# PS_DDR.net
KiCad netlist of a schematic drawn in Altium Designer
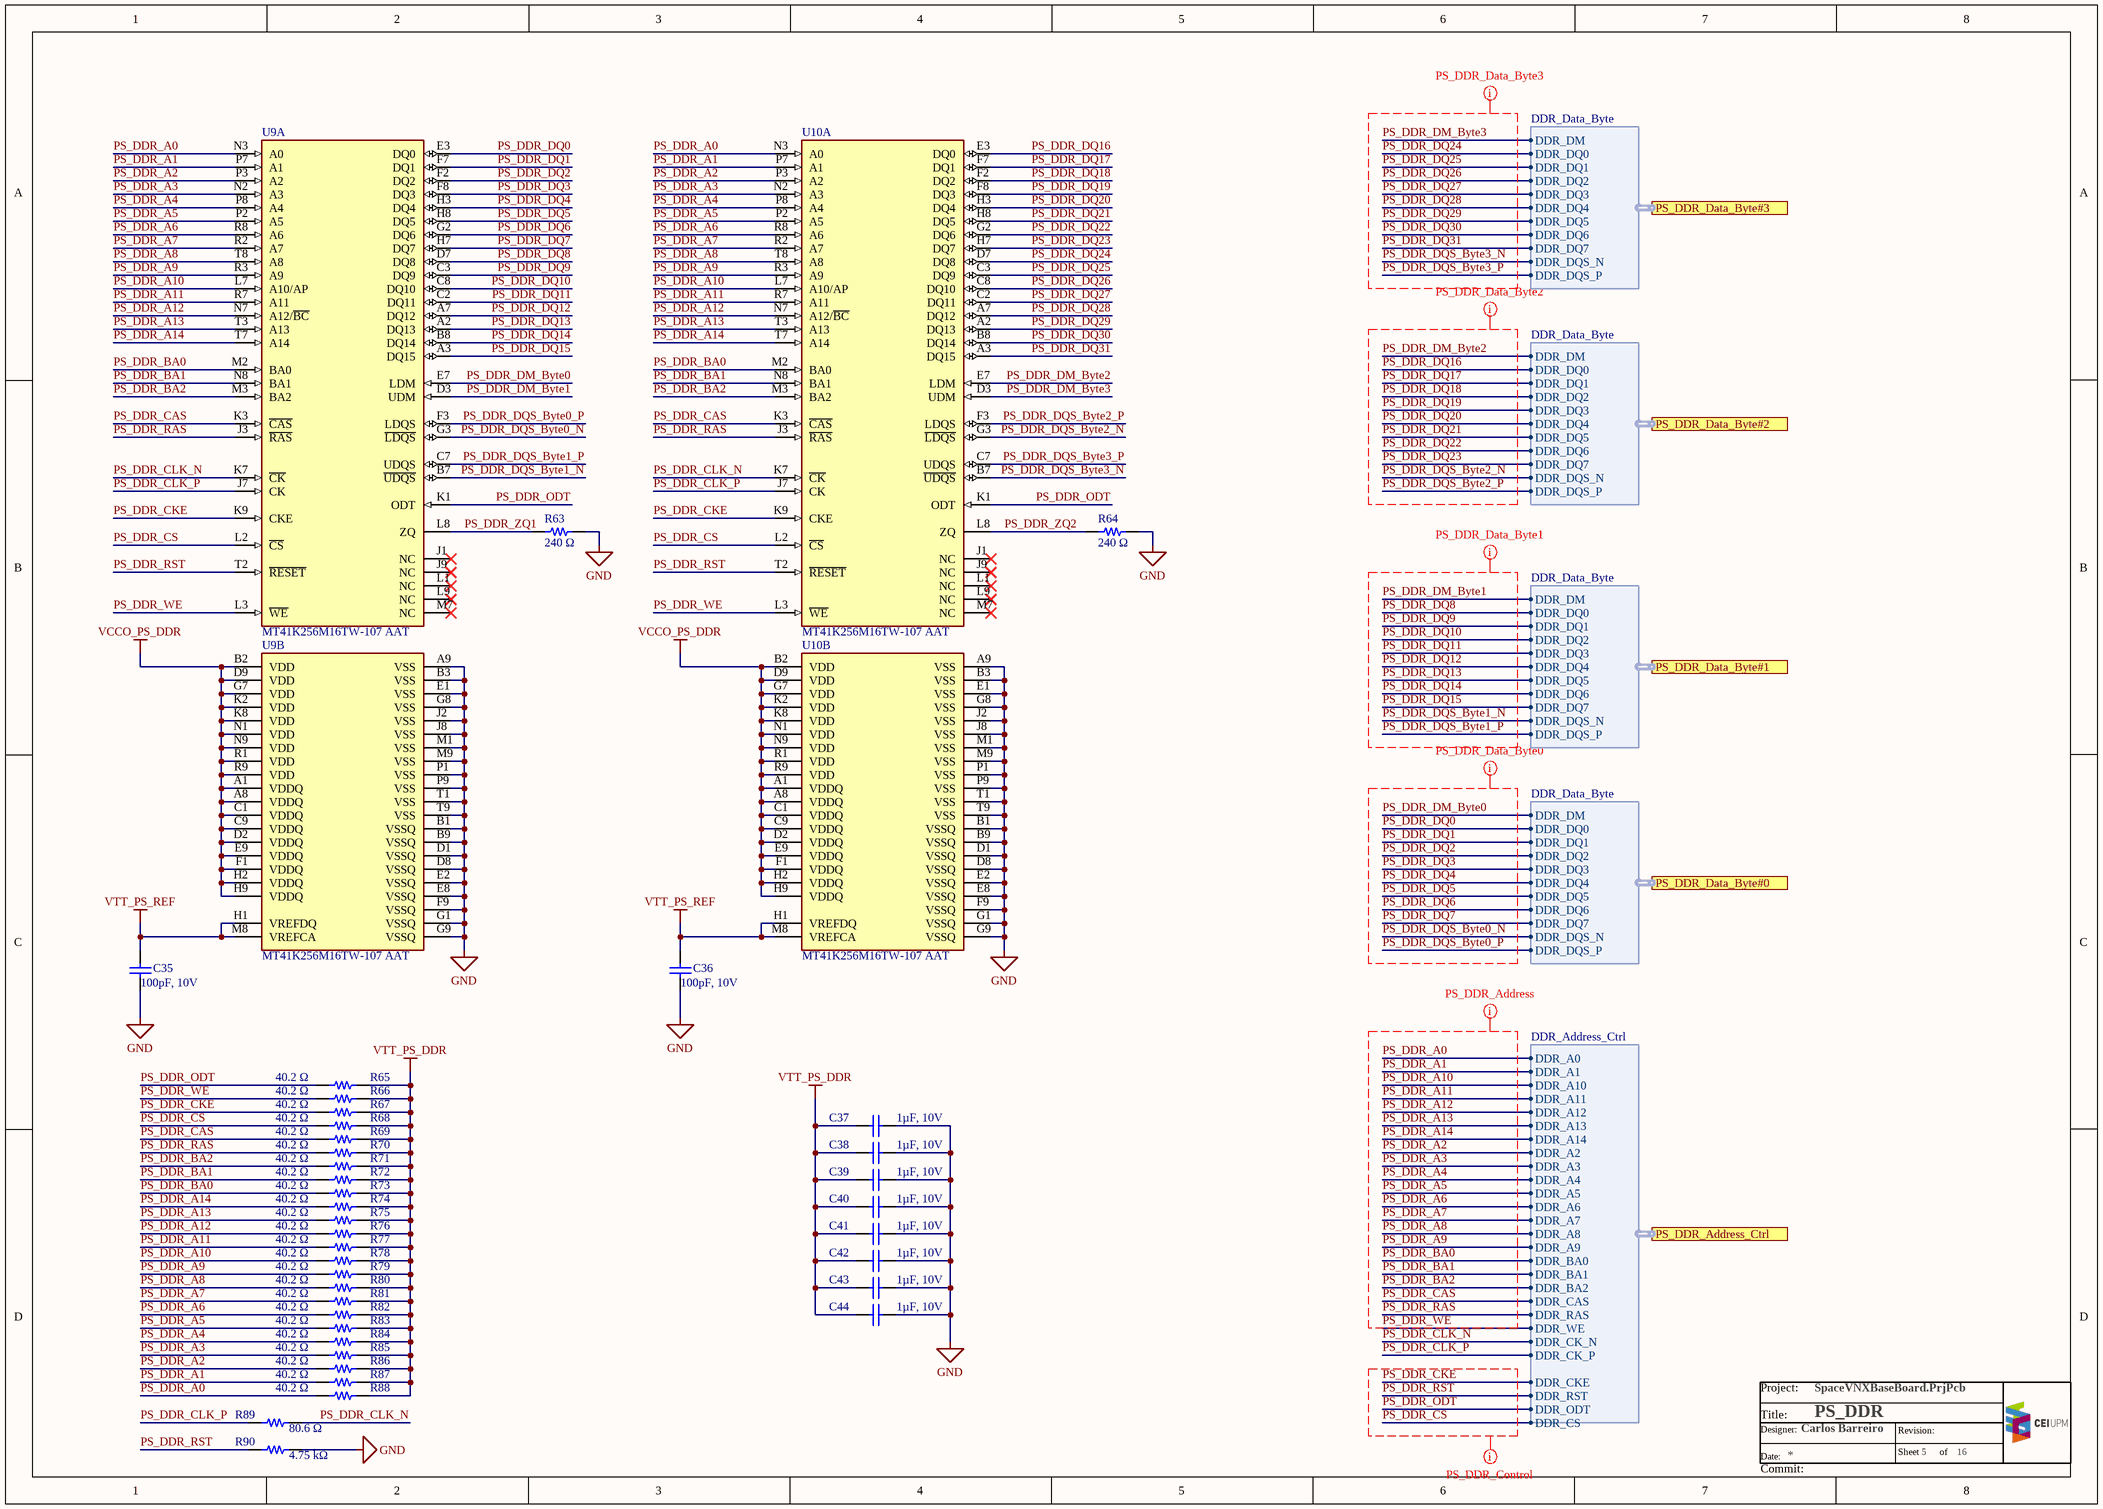
[diagram p0: PS_DDR.SchDoc]

(export (version "E")
  (design (tool "Eeschema 10.0.6"))
  (components
    (comp (ref "C35")
      (value "100pF, 10V")
      (footprint "WURTH_WCAP-CSGP_0402")
      (description "WCAP-CSGP Multilayer Ceramic Chip Capacitor, General Purpose, size 0402, NP0, 100pF, 10V")
      (fields
        (field (name "MANUFACTURER PART NUMBER") "885012005013")
        (field (name "MANUFACTURER") "Wurth Elektronik")
      )
      (libsource (lib "SpaceVNX") (part "885012005013"))
    )
    (comp (ref "C36")
      (value "100pF, 10V")
      (footprint "WURTH_WCAP-CSGP_0402")
      (description "WCAP-CSGP Multilayer Ceramic Chip Capacitor, General Purpose, size 0402, NP0, 100pF, 10V")
      (fields
        (field (name "MANUFACTURER PART NUMBER") "885012005013")
        (field (name "MANUFACTURER") "Wurth Elektronik")
      )
      (libsource (lib "SpaceVNX") (part "885012005013"))
    )
    (comp (ref "C37")
      (value "1µF, 10V")
      (footprint "WURTH_WCAP-CSGP_0402")
      (description "WCAP-CSGP Multilayer Ceramic Chip Capacitor, General Purpose, size 0402, X5R, 1uF, 10V")
      (fields
        (field (name "MANUFACTURER PART NUMBER") "885012105012")
        (field (name "MANUFACTURER") "Wurth Elektronik")
      )
      (libsource (lib "SpaceVNX") (part "885012105012"))
    )
    (comp (ref "C38")
      (value "1µF, 10V")
      (footprint "WURTH_WCAP-CSGP_0402")
      (description "WCAP-CSGP Multilayer Ceramic Chip Capacitor, General Purpose, size 0402, X5R, 1uF, 10V")
      (fields
        (field (name "MANUFACTURER PART NUMBER") "885012105012")
        (field (name "MANUFACTURER") "Wurth Elektronik")
      )
      (libsource (lib "SpaceVNX") (part "885012105012"))
    )
    (comp (ref "C39")
      (value "1µF, 10V")
      (footprint "WURTH_WCAP-CSGP_0402")
      (description "WCAP-CSGP Multilayer Ceramic Chip Capacitor, General Purpose, size 0402, X5R, 1uF, 10V")
      (fields
        (field (name "MANUFACTURER PART NUMBER") "885012105012")
        (field (name "MANUFACTURER") "Wurth Elektronik")
      )
      (libsource (lib "SpaceVNX") (part "885012105012"))
    )
    (comp (ref "C40")
      (value "1µF, 10V")
      (footprint "WURTH_WCAP-CSGP_0402")
      (description "WCAP-CSGP Multilayer Ceramic Chip Capacitor, General Purpose, size 0402, X5R, 1uF, 10V")
      (fields
        (field (name "MANUFACTURER PART NUMBER") "885012105012")
        (field (name "MANUFACTURER") "Wurth Elektronik")
      )
      (libsource (lib "SpaceVNX") (part "885012105012"))
    )
    (comp (ref "C41")
      (value "1µF, 10V")
      (footprint "WURTH_WCAP-CSGP_0402")
      (description "WCAP-CSGP Multilayer Ceramic Chip Capacitor, General Purpose, size 0402, X5R, 1uF, 10V")
      (fields
        (field (name "MANUFACTURER PART NUMBER") "885012105012")
        (field (name "MANUFACTURER") "Wurth Elektronik")
      )
      (libsource (lib "SpaceVNX") (part "885012105012"))
    )
    (comp (ref "C42")
      (value "1µF, 10V")
      (footprint "WURTH_WCAP-CSGP_0402")
      (description "WCAP-CSGP Multilayer Ceramic Chip Capacitor, General Purpose, size 0402, X5R, 1uF, 10V")
      (fields
        (field (name "MANUFACTURER PART NUMBER") "885012105012")
        (field (name "MANUFACTURER") "Wurth Elektronik")
      )
      (libsource (lib "SpaceVNX") (part "885012105012"))
    )
    (comp (ref "C43")
      (value "1µF, 10V")
      (footprint "WURTH_WCAP-CSGP_0402")
      (description "WCAP-CSGP Multilayer Ceramic Chip Capacitor, General Purpose, size 0402, X5R, 1uF, 10V")
      (fields
        (field (name "MANUFACTURER PART NUMBER") "885012105012")
        (field (name "MANUFACTURER") "Wurth Elektronik")
      )
      (libsource (lib "SpaceVNX") (part "885012105012"))
    )
    (comp (ref "C44")
      (value "1µF, 10V")
      (footprint "WURTH_WCAP-CSGP_0402")
      (description "WCAP-CSGP Multilayer Ceramic Chip Capacitor, General Purpose, size 0402, X5R, 1uF, 10V")
      (fields
        (field (name "MANUFACTURER PART NUMBER") "885012105012")
        (field (name "MANUFACTURER") "Wurth Elektronik")
      )
      (libsource (lib "SpaceVNX") (part "885012105012"))
    )
    (comp (ref "R63")
      (value "240 Ω")
      (footprint "PANASONIC_ERJ2G_0402")
      (description "General Purpose Thick Film Chip Resistors")
      (fields (field (name "MANUFACTURER") "Panasonic"))
      (libsource (lib "SpaceVNX") (part "ERJ2GEJ241X"))
    )
    (comp (ref "R64")
      (value "240 Ω")
      (footprint "PANASONIC_ERJ2G_0402")
      (description "General Purpose Thick Film Chip Resistors")
      (fields (field (name "MANUFACTURER") "Panasonic"))
      (libsource (lib "SpaceVNX") (part "ERJ2GEJ241X"))
    )
    (comp (ref "R65")
      (value "40.2 Ω")
      (footprint "PANASONIC_ERJ2G_0402")
      (description "General Purpose Thick Film Chip Resistors")
      (fields (field (name "MANUFACTURER") "Panasonic"))
      (libsource (lib "SpaceVNX") (part "ERJ2RKF40R2X"))
    )
    (comp (ref "R66")
      (value "40.2 Ω")
      (footprint "PANASONIC_ERJ2G_0402")
      (description "General Purpose Thick Film Chip Resistors")
      (fields (field (name "MANUFACTURER") "Panasonic"))
      (libsource (lib "SpaceVNX") (part "ERJ2RKF40R2X"))
    )
    (comp (ref "R67")
      (value "40.2 Ω")
      (footprint "PANASONIC_ERJ2G_0402")
      (description "General Purpose Thick Film Chip Resistors")
      (fields (field (name "MANUFACTURER") "Panasonic"))
      (libsource (lib "SpaceVNX") (part "ERJ2RKF40R2X"))
    )
    (comp (ref "R68")
      (value "40.2 Ω")
      (footprint "PANASONIC_ERJ2G_0402")
      (description "General Purpose Thick Film Chip Resistors")
      (fields (field (name "MANUFACTURER") "Panasonic"))
      (libsource (lib "SpaceVNX") (part "ERJ2RKF40R2X"))
    )
    (comp (ref "R69")
      (value "40.2 Ω")
      (footprint "PANASONIC_ERJ2G_0402")
      (description "General Purpose Thick Film Chip Resistors")
      (fields (field (name "MANUFACTURER") "Panasonic"))
      (libsource (lib "SpaceVNX") (part "ERJ2RKF40R2X"))
    )
    (comp (ref "R70")
      (value "40.2 Ω")
      (footprint "PANASONIC_ERJ2G_0402")
      (description "General Purpose Thick Film Chip Resistors")
      (fields (field (name "MANUFACTURER") "Panasonic"))
      (libsource (lib "SpaceVNX") (part "ERJ2RKF40R2X"))
    )
    (comp (ref "R71")
      (value "40.2 Ω")
      (footprint "PANASONIC_ERJ2G_0402")
      (description "General Purpose Thick Film Chip Resistors")
      (fields (field (name "MANUFACTURER") "Panasonic"))
      (libsource (lib "SpaceVNX") (part "ERJ2RKF40R2X"))
    )
    (comp (ref "R72")
      (value "40.2 Ω")
      (footprint "PANASONIC_ERJ2G_0402")
      (description "General Purpose Thick Film Chip Resistors")
      (fields (field (name "MANUFACTURER") "Panasonic"))
      (libsource (lib "SpaceVNX") (part "ERJ2RKF40R2X"))
    )
    (comp (ref "R73")
      (value "40.2 Ω")
      (footprint "PANASONIC_ERJ2G_0402")
      (description "General Purpose Thick Film Chip Resistors")
      (fields (field (name "MANUFACTURER") "Panasonic"))
      (libsource (lib "SpaceVNX") (part "ERJ2RKF40R2X"))
    )
    (comp (ref "R74")
      (value "40.2 Ω")
      (footprint "PANASONIC_ERJ2G_0402")
      (description "General Purpose Thick Film Chip Resistors")
      (fields (field (name "MANUFACTURER") "Panasonic"))
      (libsource (lib "SpaceVNX") (part "ERJ2RKF40R2X"))
    )
    (comp (ref "R75")
      (value "40.2 Ω")
      (footprint "PANASONIC_ERJ2G_0402")
      (description "General Purpose Thick Film Chip Resistors")
      (fields (field (name "MANUFACTURER") "Panasonic"))
      (libsource (lib "SpaceVNX") (part "ERJ2RKF40R2X"))
    )
    (comp (ref "R76")
      (value "40.2 Ω")
      (footprint "PANASONIC_ERJ2G_0402")
      (description "General Purpose Thick Film Chip Resistors")
      (fields (field (name "MANUFACTURER") "Panasonic"))
      (libsource (lib "SpaceVNX") (part "ERJ2RKF40R2X"))
    )
    (comp (ref "R77")
      (value "40.2 Ω")
      (footprint "PANASONIC_ERJ2G_0402")
      (description "General Purpose Thick Film Chip Resistors")
      (fields (field (name "MANUFACTURER") "Panasonic"))
      (libsource (lib "SpaceVNX") (part "ERJ2RKF40R2X"))
    )
    (comp (ref "R78")
      (value "40.2 Ω")
      (footprint "PANASONIC_ERJ2G_0402")
      (description "General Purpose Thick Film Chip Resistors")
      (fields (field (name "MANUFACTURER") "Panasonic"))
      (libsource (lib "SpaceVNX") (part "ERJ2RKF40R2X"))
    )
    (comp (ref "R79")
      (value "40.2 Ω")
      (footprint "PANASONIC_ERJ2G_0402")
      (description "General Purpose Thick Film Chip Resistors")
      (fields (field (name "MANUFACTURER") "Panasonic"))
      (libsource (lib "SpaceVNX") (part "ERJ2RKF40R2X"))
    )
    (comp (ref "R80")
      (value "40.2 Ω")
      (footprint "PANASONIC_ERJ2G_0402")
      (description "General Purpose Thick Film Chip Resistors")
      (fields (field (name "MANUFACTURER") "Panasonic"))
      (libsource (lib "SpaceVNX") (part "ERJ2RKF40R2X"))
    )
    (comp (ref "R81")
      (value "40.2 Ω")
      (footprint "PANASONIC_ERJ2G_0402")
      (description "General Purpose Thick Film Chip Resistors")
      (fields (field (name "MANUFACTURER") "Panasonic"))
      (libsource (lib "SpaceVNX") (part "ERJ2RKF40R2X"))
    )
    (comp (ref "R82")
      (value "40.2 Ω")
      (footprint "PANASONIC_ERJ2G_0402")
      (description "General Purpose Thick Film Chip Resistors")
      (fields (field (name "MANUFACTURER") "Panasonic"))
      (libsource (lib "SpaceVNX") (part "ERJ2RKF40R2X"))
    )
    (comp (ref "R83")
      (value "40.2 Ω")
      (footprint "PANASONIC_ERJ2G_0402")
      (description "General Purpose Thick Film Chip Resistors")
      (fields (field (name "MANUFACTURER") "Panasonic"))
      (libsource (lib "SpaceVNX") (part "ERJ2RKF40R2X"))
    )
    (comp (ref "R84")
      (value "40.2 Ω")
      (footprint "PANASONIC_ERJ2G_0402")
      (description "General Purpose Thick Film Chip Resistors")
      (fields (field (name "MANUFACTURER") "Panasonic"))
      (libsource (lib "SpaceVNX") (part "ERJ2RKF40R2X"))
    )
    (comp (ref "R85")
      (value "40.2 Ω")
      (footprint "PANASONIC_ERJ2G_0402")
      (description "General Purpose Thick Film Chip Resistors")
      (fields (field (name "MANUFACTURER") "Panasonic"))
      (libsource (lib "SpaceVNX") (part "ERJ2RKF40R2X"))
    )
    (comp (ref "R86")
      (value "40.2 Ω")
      (footprint "PANASONIC_ERJ2G_0402")
      (description "General Purpose Thick Film Chip Resistors")
      (fields (field (name "MANUFACTURER") "Panasonic"))
      (libsource (lib "SpaceVNX") (part "ERJ2RKF40R2X"))
    )
    (comp (ref "R87")
      (value "40.2 Ω")
      (footprint "PANASONIC_ERJ2G_0402")
      (description "General Purpose Thick Film Chip Resistors")
      (fields (field (name "MANUFACTURER") "Panasonic"))
      (libsource (lib "SpaceVNX") (part "ERJ2RKF40R2X"))
    )
    (comp (ref "R88")
      (value "40.2 Ω")
      (footprint "PANASONIC_ERJ2G_0402")
      (description "General Purpose Thick Film Chip Resistors")
      (fields (field (name "MANUFACTURER") "Panasonic"))
      (libsource (lib "SpaceVNX") (part "ERJ2RKF40R2X"))
    )
    (comp (ref "R89")
      (value "80.6 Ω")
      (footprint "PANASONIC_ERJ2G_0402")
      (description "General Purpose Thick Film Chip Resistors")
      (fields (field (name "MANUFACTURER") "Panasonic"))
      (libsource (lib "SpaceVNX") (part "ERJ2RKF80R6X"))
    )
    (comp (ref "R90")
      (value "4.75 kΩ")
      (footprint "PANASONIC_ERJ2G_0402")
      (description "General Purpose Thick Film Chip Resistors")
      (fields (field (name "MANUFACTURER") "Panasonic"))
      (libsource (lib "SpaceVNX") (part "ERJ2RKF4751X"))
    )
    (comp (ref "U9")
      (value "MT41K256M16TW-107 AAT")
      (footprint "Micron_TW")
      (description "DDR3L SDRAM")
      (libsource (lib "SpaceVNX") (part "MT41K256M16TW-107 AAT"))
    )
    (comp (ref "U10")
      (value "MT41K256M16TW-107 AAT")
      (footprint "Micron_TW")
      (description "DDR3L SDRAM")
      (libsource (lib "SpaceVNX") (part "MT41K256M16TW-107 AAT"))
    )
  )
  (nets
    (net (code "3") (name "/PS_DDR_A0") (class "Default")
      (node (ref "R88") (pin "2") (pinfunction "2_2") (pintype "passive"))
      (node (ref "U10") (pin "N3") (pinfunction "A0_N3") (pintype "input"))
      (node (ref "U9") (pin "N3") (pinfunction "A0_N3") (pintype "input"))
    )
    (net (code "4") (name "/PS_DDR_A1") (class "Default")
      (node (ref "R87") (pin "2") (pinfunction "2_2") (pintype "passive"))
      (node (ref "U10") (pin "P7") (pinfunction "A1_P7") (pintype "input"))
      (node (ref "U9") (pin "P7") (pinfunction "A1_P7") (pintype "input"))
    )
    (net (code "5") (name "/PS_DDR_A2") (class "Default")
      (node (ref "R86") (pin "2") (pinfunction "2_2") (pintype "passive"))
      (node (ref "U10") (pin "P3") (pinfunction "A2_P3") (pintype "input"))
      (node (ref "U9") (pin "P3") (pinfunction "A2_P3") (pintype "input"))
    )
    (net (code "6") (name "/PS_DDR_A3") (class "Default")
      (node (ref "R85") (pin "2") (pinfunction "2_2") (pintype "passive"))
      (node (ref "U10") (pin "N2") (pinfunction "A3_N2") (pintype "input"))
      (node (ref "U9") (pin "N2") (pinfunction "A3_N2") (pintype "input"))
    )
    (net (code "7") (name "/PS_DDR_A4") (class "Default")
      (node (ref "R84") (pin "2") (pinfunction "2_2") (pintype "passive"))
      (node (ref "U10") (pin "P8") (pinfunction "A4_P8") (pintype "input"))
      (node (ref "U9") (pin "P8") (pinfunction "A4_P8") (pintype "input"))
    )
    (net (code "8") (name "/PS_DDR_A5") (class "Default")
      (node (ref "R83") (pin "2") (pinfunction "2_2") (pintype "passive"))
      (node (ref "U10") (pin "P2") (pinfunction "A5_P2") (pintype "input"))
      (node (ref "U9") (pin "P2") (pinfunction "A5_P2") (pintype "input"))
    )
    (net (code "9") (name "/PS_DDR_A6") (class "Default")
      (node (ref "R82") (pin "2") (pinfunction "2_2") (pintype "passive"))
      (node (ref "U10") (pin "R8") (pinfunction "A6_R8") (pintype "input"))
      (node (ref "U9") (pin "R8") (pinfunction "A6_R8") (pintype "input"))
    )
    (net (code "10") (name "/PS_DDR_A7") (class "Default")
      (node (ref "R81") (pin "2") (pinfunction "2_2") (pintype "passive"))
      (node (ref "U10") (pin "R2") (pinfunction "A7_R2") (pintype "input"))
      (node (ref "U9") (pin "R2") (pinfunction "A7_R2") (pintype "input"))
    )
    (net (code "11") (name "/PS_DDR_A8") (class "Default")
      (node (ref "R80") (pin "2") (pinfunction "2_2") (pintype "passive"))
      (node (ref "U10") (pin "T8") (pinfunction "A8_T8") (pintype "input"))
      (node (ref "U9") (pin "T8") (pinfunction "A8_T8") (pintype "input"))
    )
    (net (code "12") (name "/PS_DDR_A9") (class "Default")
      (node (ref "R79") (pin "2") (pinfunction "2_2") (pintype "passive"))
      (node (ref "U10") (pin "R3") (pinfunction "A9_R3") (pintype "input"))
      (node (ref "U9") (pin "R3") (pinfunction "A9_R3") (pintype "input"))
    )
    (net (code "13") (name "/PS_DDR_A10") (class "Default")
      (node (ref "R78") (pin "2") (pinfunction "2_2") (pintype "passive"))
      (node (ref "U10") (pin "L7") (pinfunction "A10/AP_L7") (pintype "input"))
      (node (ref "U9") (pin "L7") (pinfunction "A10/AP_L7") (pintype "input"))
    )
    (net (code "14") (name "/PS_DDR_A11") (class "Default")
      (node (ref "R77") (pin "2") (pinfunction "2_2") (pintype "passive"))
      (node (ref "U10") (pin "R7") (pinfunction "A11_R7") (pintype "input"))
      (node (ref "U9") (pin "R7") (pinfunction "A11_R7") (pintype "input"))
    )
    (net (code "15") (name "/PS_DDR_A12") (class "Default")
      (node (ref "R76") (pin "2") (pinfunction "2_2") (pintype "passive"))
      (node (ref "U10") (pin "N7") (pinfunction "A12/~{BC}_N7") (pintype "input"))
      (node (ref "U9") (pin "N7") (pinfunction "A12/~{BC}_N7") (pintype "input"))
    )
    (net (code "16") (name "/PS_DDR_A13") (class "Default")
      (node (ref "R75") (pin "2") (pinfunction "2_2") (pintype "passive"))
      (node (ref "U10") (pin "T3") (pinfunction "A13_T3") (pintype "input"))
      (node (ref "U9") (pin "T3") (pinfunction "A13_T3") (pintype "input"))
    )
    (net (code "17") (name "/PS_DDR_A14") (class "Default")
      (node (ref "R74") (pin "2") (pinfunction "2_2") (pintype "passive"))
      (node (ref "U10") (pin "T7") (pinfunction "A14_T7") (pintype "input"))
      (node (ref "U9") (pin "T7") (pinfunction "A14_T7") (pintype "input"))
    )
    (net (code "18") (name "/PS_DDR_BA0") (class "Default")
      (node (ref "R73") (pin "2") (pinfunction "2_2") (pintype "passive"))
      (node (ref "U10") (pin "M2") (pinfunction "BA0_M2") (pintype "input"))
      (node (ref "U9") (pin "M2") (pinfunction "BA0_M2") (pintype "input"))
    )
    (net (code "19") (name "/PS_DDR_BA1") (class "Default")
      (node (ref "R72") (pin "2") (pinfunction "2_2") (pintype "passive"))
      (node (ref "U10") (pin "N8") (pinfunction "BA1_N8") (pintype "input"))
      (node (ref "U9") (pin "N8") (pinfunction "BA1_N8") (pintype "input"))
    )
    (net (code "20") (name "/PS_DDR_BA2") (class "Default")
      (node (ref "R71") (pin "2") (pinfunction "2_2") (pintype "passive"))
      (node (ref "U10") (pin "M3") (pinfunction "BA2_M3") (pintype "input"))
      (node (ref "U9") (pin "M3") (pinfunction "BA2_M3") (pintype "input"))
    )
    (net (code "21") (name "/PS_DDR_CAS") (class "Default")
      (node (ref "R69") (pin "2") (pinfunction "2_2") (pintype "passive"))
      (node (ref "U10") (pin "K3") (pinfunction "~{CAS}_K3") (pintype "input"))
      (node (ref "U9") (pin "K3") (pinfunction "~{CAS}_K3") (pintype "input"))
    )
    (net (code "22") (name "/PS_DDR_CKE") (class "Default")
      (node (ref "R67") (pin "2") (pinfunction "2_2") (pintype "passive"))
      (node (ref "U10") (pin "K9") (pinfunction "CKE_K9") (pintype "input"))
      (node (ref "U9") (pin "K9") (pinfunction "CKE_K9") (pintype "input"))
    )
    (net (code "23") (name "/PS_DDR_CLK_N") (class "Default")
      (node (ref "R89") (pin "2") (pinfunction "2_2") (pintype "passive"))
      (node (ref "U10") (pin "K7") (pinfunction "~{CK}_K7") (pintype "input"))
      (node (ref "U9") (pin "K7") (pinfunction "~{CK}_K7") (pintype "input"))
    )
    (net (code "24") (name "/PS_DDR_CLK_P") (class "Default")
      (node (ref "R89") (pin "1") (pinfunction "1_1") (pintype "passive"))
      (node (ref "U10") (pin "J7") (pinfunction "CK_J7") (pintype "input"))
      (node (ref "U9") (pin "J7") (pinfunction "CK_J7") (pintype "input"))
    )
    (net (code "25") (name "/PS_DDR_CS") (class "Default")
      (node (ref "R68") (pin "2") (pinfunction "2_2") (pintype "passive"))
      (node (ref "U10") (pin "L2") (pinfunction "~{CS}_L2") (pintype "input"))
      (node (ref "U9") (pin "L2") (pinfunction "~{CS}_L2") (pintype "input"))
    )
    (net (code "26") (name "/PS_DDR_DM_Byte0") (class "Default")
      (node (ref "U9") (pin "E7") (pinfunction "LDM_E7") (pintype "input"))
    )
    (net (code "27") (name "/PS_DDR_DM_Byte1") (class "Default")
      (node (ref "U9") (pin "D3") (pinfunction "UDM_D3") (pintype "input"))
    )
    (net (code "28") (name "/PS_DDR_DM_Byte2") (class "Default")
      (node (ref "U10") (pin "E7") (pinfunction "LDM_E7") (pintype "input"))
    )
    (net (code "29") (name "/PS_DDR_DM_Byte3") (class "Default")
      (node (ref "U10") (pin "D3") (pinfunction "UDM_D3") (pintype "input"))
    )
    (net (code "30") (name "/PS_DDR_DQ0") (class "Default")
      (node (ref "U9") (pin "E3") (pinfunction "DQ0_E3") (pintype "bidirectional"))
    )
    (net (code "31") (name "/PS_DDR_DQ1") (class "Default")
      (node (ref "U9") (pin "F7") (pinfunction "DQ1_F7") (pintype "bidirectional"))
    )
    (net (code "32") (name "/PS_DDR_DQ2") (class "Default")
      (node (ref "U9") (pin "F2") (pinfunction "DQ2_F2") (pintype "bidirectional"))
    )
    (net (code "33") (name "/PS_DDR_DQ3") (class "Default")
      (node (ref "U9") (pin "F8") (pinfunction "DQ3_F8") (pintype "bidirectional"))
    )
    (net (code "34") (name "/PS_DDR_DQ4") (class "Default")
      (node (ref "U9") (pin "H3") (pinfunction "DQ4_H3") (pintype "bidirectional"))
    )
    (net (code "35") (name "/PS_DDR_DQ5") (class "Default")
      (node (ref "U9") (pin "H8") (pinfunction "DQ5_H8") (pintype "bidirectional"))
    )
    (net (code "36") (name "/PS_DDR_DQ6") (class "Default")
      (node (ref "U9") (pin "G2") (pinfunction "DQ6_G2") (pintype "bidirectional"))
    )
    (net (code "37") (name "/PS_DDR_DQ7") (class "Default")
      (node (ref "U9") (pin "H7") (pinfunction "DQ7_H7") (pintype "bidirectional"))
    )
    (net (code "38") (name "/PS_DDR_DQ8") (class "Default")
      (node (ref "U9") (pin "D7") (pinfunction "DQ8_D7") (pintype "bidirectional"))
    )
    (net (code "39") (name "/PS_DDR_DQ9") (class "Default")
      (node (ref "U9") (pin "C3") (pinfunction "DQ9_C3") (pintype "bidirectional"))
    )
    (net (code "40") (name "/PS_DDR_DQ10") (class "Default")
      (node (ref "U9") (pin "C8") (pinfunction "DQ10_C8") (pintype "bidirectional"))
    )
    (net (code "41") (name "/PS_DDR_DQ11") (class "Default")
      (node (ref "U9") (pin "C2") (pinfunction "DQ11_C2") (pintype "bidirectional"))
    )
    (net (code "42") (name "/PS_DDR_DQ12") (class "Default")
      (node (ref "U9") (pin "A7") (pinfunction "DQ12_A7") (pintype "bidirectional"))
    )
    (net (code "43") (name "/PS_DDR_DQ13") (class "Default")
      (node (ref "U9") (pin "A2") (pinfunction "DQ13_A2") (pintype "bidirectional"))
    )
    (net (code "44") (name "/PS_DDR_DQ14") (class "Default")
      (node (ref "U9") (pin "B8") (pinfunction "DQ14_B8") (pintype "bidirectional"))
    )
    (net (code "45") (name "/PS_DDR_DQ15") (class "Default")
      (node (ref "U9") (pin "A3") (pinfunction "DQ15_A3") (pintype "bidirectional"))
    )
    (net (code "46") (name "/PS_DDR_DQ16") (class "Default")
      (node (ref "U10") (pin "E3") (pinfunction "DQ0_E3") (pintype "bidirectional"))
    )
    (net (code "47") (name "/PS_DDR_DQ17") (class "Default")
      (node (ref "U10") (pin "F7") (pinfunction "DQ1_F7") (pintype "bidirectional"))
    )
    (net (code "48") (name "/PS_DDR_DQ18") (class "Default")
      (node (ref "U10") (pin "F2") (pinfunction "DQ2_F2") (pintype "bidirectional"))
    )
    (net (code "49") (name "/PS_DDR_DQ19") (class "Default")
      (node (ref "U10") (pin "F8") (pinfunction "DQ3_F8") (pintype "bidirectional"))
    )
    (net (code "50") (name "/PS_DDR_DQ20") (class "Default")
      (node (ref "U10") (pin "H3") (pinfunction "DQ4_H3") (pintype "bidirectional"))
    )
    (net (code "51") (name "/PS_DDR_DQ21") (class "Default")
      (node (ref "U10") (pin "H8") (pinfunction "DQ5_H8") (pintype "bidirectional"))
    )
    (net (code "52") (name "/PS_DDR_DQ22") (class "Default")
      (node (ref "U10") (pin "G2") (pinfunction "DQ6_G2") (pintype "bidirectional"))
    )
    (net (code "53") (name "/PS_DDR_DQ23") (class "Default")
      (node (ref "U10") (pin "H7") (pinfunction "DQ7_H7") (pintype "bidirectional"))
    )
    (net (code "54") (name "/PS_DDR_DQ24") (class "Default")
      (node (ref "U10") (pin "D7") (pinfunction "DQ8_D7") (pintype "bidirectional"))
    )
    (net (code "55") (name "/PS_DDR_DQ25") (class "Default")
      (node (ref "U10") (pin "C3") (pinfunction "DQ9_C3") (pintype "bidirectional"))
    )
    (net (code "56") (name "/PS_DDR_DQ26") (class "Default")
      (node (ref "U10") (pin "C8") (pinfunction "DQ10_C8") (pintype "bidirectional"))
    )
    (net (code "57") (name "/PS_DDR_DQ27") (class "Default")
      (node (ref "U10") (pin "C2") (pinfunction "DQ11_C2") (pintype "bidirectional"))
    )
    (net (code "58") (name "/PS_DDR_DQ28") (class "Default")
      (node (ref "U10") (pin "A7") (pinfunction "DQ12_A7") (pintype "bidirectional"))
    )
    (net (code "59") (name "/PS_DDR_DQ29") (class "Default")
      (node (ref "U10") (pin "A2") (pinfunction "DQ13_A2") (pintype "bidirectional"))
    )
    (net (code "60") (name "/PS_DDR_DQ30") (class "Default")
      (node (ref "U10") (pin "B8") (pinfunction "DQ14_B8") (pintype "bidirectional"))
    )
    (net (code "61") (name "/PS_DDR_DQ31") (class "Default")
      (node (ref "U10") (pin "A3") (pinfunction "DQ15_A3") (pintype "bidirectional"))
    )
    (net (code "62") (name "/PS_DDR_DQS_Byte0_N") (class "Default")
      (node (ref "U9") (pin "G3") (pinfunction "~{LDQS}_G3") (pintype "bidirectional"))
    )
    (net (code "63") (name "/PS_DDR_DQS_Byte0_P") (class "Default")
      (node (ref "U9") (pin "F3") (pinfunction "LDQS_F3") (pintype "bidirectional"))
    )
    (net (code "64") (name "/PS_DDR_DQS_Byte1_N") (class "Default")
      (node (ref "U9") (pin "B7") (pinfunction "~{UDQS}_B7") (pintype "bidirectional"))
    )
    (net (code "65") (name "/PS_DDR_DQS_Byte1_P") (class "Default")
      (node (ref "U9") (pin "C7") (pinfunction "UDQS_C7") (pintype "bidirectional"))
    )
    (net (code "66") (name "/PS_DDR_DQS_Byte2_N") (class "Default")
      (node (ref "U10") (pin "G3") (pinfunction "~{LDQS}_G3") (pintype "bidirectional"))
    )
    (net (code "67") (name "/PS_DDR_DQS_Byte2_P") (class "Default")
      (node (ref "U10") (pin "F3") (pinfunction "LDQS_F3") (pintype "bidirectional"))
    )
    (net (code "68") (name "/PS_DDR_DQS_Byte3_N") (class "Default")
      (node (ref "U10") (pin "B7") (pinfunction "~{UDQS}_B7") (pintype "bidirectional"))
    )
    (net (code "69") (name "/PS_DDR_DQS_Byte3_P") (class "Default")
      (node (ref "U10") (pin "C7") (pinfunction "UDQS_C7") (pintype "bidirectional"))
    )
    (net (code "70") (name "/PS_DDR_ODT") (class "Default")
      (node (ref "R65") (pin "2") (pinfunction "2_2") (pintype "passive"))
      (node (ref "U10") (pin "K1") (pinfunction "ODT_K1") (pintype "input"))
      (node (ref "U9") (pin "K1") (pinfunction "ODT_K1") (pintype "input"))
    )
    (net (code "71") (name "/PS_DDR_RAS") (class "Default")
      (node (ref "R70") (pin "2") (pinfunction "2_2") (pintype "passive"))
      (node (ref "U10") (pin "J3") (pinfunction "~{RAS}_J3") (pintype "input"))
      (node (ref "U9") (pin "J3") (pinfunction "~{RAS}_J3") (pintype "input"))
    )
    (net (code "72") (name "/PS_DDR_RST") (class "Default")
      (node (ref "R90") (pin "1") (pinfunction "1_1") (pintype "passive"))
      (node (ref "U10") (pin "T2") (pinfunction "~{RESET}_T2") (pintype "input"))
      (node (ref "U9") (pin "T2") (pinfunction "~{RESET}_T2") (pintype "input"))
    )
    (net (code "73") (name "/PS_DDR_WE") (class "Default")
      (node (ref "R66") (pin "2") (pinfunction "2_2") (pintype "passive"))
      (node (ref "U10") (pin "L3") (pinfunction "~{WE}_L3") (pintype "input"))
      (node (ref "U9") (pin "L3") (pinfunction "~{WE}_L3") (pintype "input"))
    )
    (net (code "74") (name "/PS_DDR_ZQ1") (class "Default")
      (node (ref "R63") (pin "1") (pinfunction "1_1") (pintype "passive"))
      (node (ref "U9") (pin "L8") (pinfunction "ZQ_L8") (pintype "passive"))
    )
    (net (code "75") (name "/PS_DDR_ZQ2") (class "Default")
      (node (ref "R64") (pin "1") (pinfunction "1_1") (pintype "passive"))
      (node (ref "U10") (pin "L8") (pinfunction "ZQ_L8") (pintype "passive"))
    )
    (net (code "78") (name "GND") (class "Default")
      (node (ref "C35") (pin "1") (pinfunction "1_1") (pintype "passive"))
      (node (ref "C36") (pin "1") (pinfunction "1_1") (pintype "passive"))
      (node (ref "C37") (pin "1") (pinfunction "1_1") (pintype "passive"))
      (node (ref "C38") (pin "1") (pinfunction "1_1") (pintype "passive"))
      (node (ref "C39") (pin "1") (pinfunction "1_1") (pintype "passive"))
      (node (ref "C40") (pin "1") (pinfunction "1_1") (pintype "passive"))
      (node (ref "C41") (pin "1") (pinfunction "1_1") (pintype "passive"))
      (node (ref "C42") (pin "1") (pinfunction "1_1") (pintype "passive"))
      (node (ref "C43") (pin "1") (pinfunction "1_1") (pintype "passive"))
      (node (ref "C44") (pin "1") (pinfunction "1_1") (pintype "passive"))
      (node (ref "R63") (pin "2") (pinfunction "2_2") (pintype "passive"))
      (node (ref "R64") (pin "2") (pinfunction "2_2") (pintype "passive"))
      (node (ref "R90") (pin "2") (pinfunction "2_2") (pintype "passive"))
      (node (ref "U10") (pin "A9") (pinfunction "VSS_A9") (pintype "power_in"))
      (node (ref "U10") (pin "B1") (pinfunction "VSSQ_B1") (pintype "power_in"))
      (node (ref "U10") (pin "B3") (pinfunction "VSS_B3") (pintype "power_in"))
      (node (ref "U10") (pin "B9") (pinfunction "VSSQ_B9") (pintype "power_in"))
      (node (ref "U10") (pin "D1") (pinfunction "VSSQ_D1") (pintype "power_in"))
      (node (ref "U10") (pin "D8") (pinfunction "VSSQ_D8") (pintype "power_in"))
      (node (ref "U10") (pin "E1") (pinfunction "VSS_E1") (pintype "power_in"))
      (node (ref "U10") (pin "E2") (pinfunction "VSSQ_E2") (pintype "power_in"))
      (node (ref "U10") (pin "E8") (pinfunction "VSSQ_E8") (pintype "power_in"))
      (node (ref "U10") (pin "F9") (pinfunction "VSSQ_F9") (pintype "power_in"))
      (node (ref "U10") (pin "G1") (pinfunction "VSSQ_G1") (pintype "power_in"))
      (node (ref "U10") (pin "G8") (pinfunction "VSS_G8") (pintype "power_in"))
      (node (ref "U10") (pin "G9") (pinfunction "VSSQ_G9") (pintype "power_in"))
      (node (ref "U10") (pin "J2") (pinfunction "VSS_J2") (pintype "power_in"))
      (node (ref "U10") (pin "J8") (pinfunction "VSS_J8") (pintype "power_in"))
      (node (ref "U10") (pin "M1") (pinfunction "VSS_M1") (pintype "power_in"))
      (node (ref "U10") (pin "M9") (pinfunction "VSS_M9") (pintype "power_in"))
      (node (ref "U10") (pin "P1") (pinfunction "VSS_P1") (pintype "power_in"))
      (node (ref "U10") (pin "P9") (pinfunction "VSS_P9") (pintype "power_in"))
      (node (ref "U10") (pin "T1") (pinfunction "VSS_T1") (pintype "power_in"))
      (node (ref "U10") (pin "T9") (pinfunction "VSS_T9") (pintype "power_in"))
      (node (ref "U9") (pin "A9") (pinfunction "VSS_A9") (pintype "power_in"))
      (node (ref "U9") (pin "B1") (pinfunction "VSSQ_B1") (pintype "power_in"))
      (node (ref "U9") (pin "B3") (pinfunction "VSS_B3") (pintype "power_in"))
      (node (ref "U9") (pin "B9") (pinfunction "VSSQ_B9") (pintype "power_in"))
      (node (ref "U9") (pin "D1") (pinfunction "VSSQ_D1") (pintype "power_in"))
      (node (ref "U9") (pin "D8") (pinfunction "VSSQ_D8") (pintype "power_in"))
      (node (ref "U9") (pin "E1") (pinfunction "VSS_E1") (pintype "power_in"))
      (node (ref "U9") (pin "E2") (pinfunction "VSSQ_E2") (pintype "power_in"))
      (node (ref "U9") (pin "E8") (pinfunction "VSSQ_E8") (pintype "power_in"))
      (node (ref "U9") (pin "F9") (pinfunction "VSSQ_F9") (pintype "power_in"))
      (node (ref "U9") (pin "G1") (pinfunction "VSSQ_G1") (pintype "power_in"))
      (node (ref "U9") (pin "G8") (pinfunction "VSS_G8") (pintype "power_in"))
      (node (ref "U9") (pin "G9") (pinfunction "VSSQ_G9") (pintype "power_in"))
      (node (ref "U9") (pin "J2") (pinfunction "VSS_J2") (pintype "power_in"))
      (node (ref "U9") (pin "J8") (pinfunction "VSS_J8") (pintype "power_in"))
      (node (ref "U9") (pin "M1") (pinfunction "VSS_M1") (pintype "power_in"))
      (node (ref "U9") (pin "M9") (pinfunction "VSS_M9") (pintype "power_in"))
      (node (ref "U9") (pin "P1") (pinfunction "VSS_P1") (pintype "power_in"))
      (node (ref "U9") (pin "P9") (pinfunction "VSS_P9") (pintype "power_in"))
      (node (ref "U9") (pin "T1") (pinfunction "VSS_T1") (pintype "power_in"))
      (node (ref "U9") (pin "T9") (pinfunction "VSS_T9") (pintype "power_in"))
    )
    (net (code "79") (name "VCCO_PS_DDR") (class "Default")
      (node (ref "U10") (pin "A1") (pinfunction "VDDQ_A1") (pintype "power_in"))
      (node (ref "U10") (pin "A8") (pinfunction "VDDQ_A8") (pintype "power_in"))
      (node (ref "U10") (pin "B2") (pinfunction "VDD_B2") (pintype "power_in"))
      (node (ref "U10") (pin "C1") (pinfunction "VDDQ_C1") (pintype "power_in"))
      (node (ref "U10") (pin "C9") (pinfunction "VDDQ_C9") (pintype "power_in"))
      (node (ref "U10") (pin "D2") (pinfunction "VDDQ_D2") (pintype "power_in"))
      (node (ref "U10") (pin "D9") (pinfunction "VDD_D9") (pintype "power_in"))
      (node (ref "U10") (pin "E9") (pinfunction "VDDQ_E9") (pintype "power_in"))
      (node (ref "U10") (pin "F1") (pinfunction "VDDQ_F1") (pintype "power_in"))
      (node (ref "U10") (pin "G7") (pinfunction "VDD_G7") (pintype "power_in"))
      (node (ref "U10") (pin "H2") (pinfunction "VDDQ_H2") (pintype "power_in"))
      (node (ref "U10") (pin "H9") (pinfunction "VDDQ_H9") (pintype "power_in"))
      (node (ref "U10") (pin "K2") (pinfunction "VDD_K2") (pintype "power_in"))
      (node (ref "U10") (pin "K8") (pinfunction "VDD_K8") (pintype "power_in"))
      (node (ref "U10") (pin "N1") (pinfunction "VDD_N1") (pintype "power_in"))
      (node (ref "U10") (pin "N9") (pinfunction "VDD_N9") (pintype "power_in"))
      (node (ref "U10") (pin "R1") (pinfunction "VDD_R1") (pintype "power_in"))
      (node (ref "U10") (pin "R9") (pinfunction "VDD_R9") (pintype "power_in"))
      (node (ref "U9") (pin "A1") (pinfunction "VDDQ_A1") (pintype "power_in"))
      (node (ref "U9") (pin "A8") (pinfunction "VDDQ_A8") (pintype "power_in"))
      (node (ref "U9") (pin "B2") (pinfunction "VDD_B2") (pintype "power_in"))
      (node (ref "U9") (pin "C1") (pinfunction "VDDQ_C1") (pintype "power_in"))
      (node (ref "U9") (pin "C9") (pinfunction "VDDQ_C9") (pintype "power_in"))
      (node (ref "U9") (pin "D2") (pinfunction "VDDQ_D2") (pintype "power_in"))
      (node (ref "U9") (pin "D9") (pinfunction "VDD_D9") (pintype "power_in"))
      (node (ref "U9") (pin "E9") (pinfunction "VDDQ_E9") (pintype "power_in"))
      (node (ref "U9") (pin "F1") (pinfunction "VDDQ_F1") (pintype "power_in"))
      (node (ref "U9") (pin "G7") (pinfunction "VDD_G7") (pintype "power_in"))
      (node (ref "U9") (pin "H2") (pinfunction "VDDQ_H2") (pintype "power_in"))
      (node (ref "U9") (pin "H9") (pinfunction "VDDQ_H9") (pintype "power_in"))
      (node (ref "U9") (pin "K2") (pinfunction "VDD_K2") (pintype "power_in"))
      (node (ref "U9") (pin "K8") (pinfunction "VDD_K8") (pintype "power_in"))
      (node (ref "U9") (pin "N1") (pinfunction "VDD_N1") (pintype "power_in"))
      (node (ref "U9") (pin "N9") (pinfunction "VDD_N9") (pintype "power_in"))
      (node (ref "U9") (pin "R1") (pinfunction "VDD_R1") (pintype "power_in"))
      (node (ref "U9") (pin "R9") (pinfunction "VDD_R9") (pintype "power_in"))
    )
    (net (code "80") (name "VTT_PS_DDR") (class "Default")
      (node (ref "C37") (pin "2") (pinfunction "2_2") (pintype "passive"))
      (node (ref "C38") (pin "2") (pinfunction "2_2") (pintype "passive"))
      (node (ref "C39") (pin "2") (pinfunction "2_2") (pintype "passive"))
      (node (ref "C40") (pin "2") (pinfunction "2_2") (pintype "passive"))
      (node (ref "C41") (pin "2") (pinfunction "2_2") (pintype "passive"))
      (node (ref "C42") (pin "2") (pinfunction "2_2") (pintype "passive"))
      (node (ref "C43") (pin "2") (pinfunction "2_2") (pintype "passive"))
      (node (ref "C44") (pin "2") (pinfunction "2_2") (pintype "passive"))
      (node (ref "R65") (pin "1") (pinfunction "1_1") (pintype "passive"))
      (node (ref "R66") (pin "1") (pinfunction "1_1") (pintype "passive"))
      (node (ref "R67") (pin "1") (pinfunction "1_1") (pintype "passive"))
      (node (ref "R68") (pin "1") (pinfunction "1_1") (pintype "passive"))
      (node (ref "R69") (pin "1") (pinfunction "1_1") (pintype "passive"))
      (node (ref "R70") (pin "1") (pinfunction "1_1") (pintype "passive"))
      (node (ref "R71") (pin "1") (pinfunction "1_1") (pintype "passive"))
      (node (ref "R72") (pin "1") (pinfunction "1_1") (pintype "passive"))
      (node (ref "R73") (pin "1") (pinfunction "1_1") (pintype "passive"))
      (node (ref "R74") (pin "1") (pinfunction "1_1") (pintype "passive"))
      (node (ref "R75") (pin "1") (pinfunction "1_1") (pintype "passive"))
      (node (ref "R76") (pin "1") (pinfunction "1_1") (pintype "passive"))
      (node (ref "R77") (pin "1") (pinfunction "1_1") (pintype "passive"))
      (node (ref "R78") (pin "1") (pinfunction "1_1") (pintype "passive"))
      (node (ref "R79") (pin "1") (pinfunction "1_1") (pintype "passive"))
      (node (ref "R80") (pin "1") (pinfunction "1_1") (pintype "passive"))
      (node (ref "R81") (pin "1") (pinfunction "1_1") (pintype "passive"))
      (node (ref "R82") (pin "1") (pinfunction "1_1") (pintype "passive"))
      (node (ref "R83") (pin "1") (pinfunction "1_1") (pintype "passive"))
      (node (ref "R84") (pin "1") (pinfunction "1_1") (pintype "passive"))
      (node (ref "R85") (pin "1") (pinfunction "1_1") (pintype "passive"))
      (node (ref "R86") (pin "1") (pinfunction "1_1") (pintype "passive"))
      (node (ref "R87") (pin "1") (pinfunction "1_1") (pintype "passive"))
      (node (ref "R88") (pin "1") (pinfunction "1_1") (pintype "passive"))
    )
    (net (code "81") (name "VTT_PS_REF") (class "Default")
      (node (ref "C35") (pin "2") (pinfunction "2_2") (pintype "passive"))
      (node (ref "C36") (pin "2") (pinfunction "2_2") (pintype "passive"))
      (node (ref "U10") (pin "H1") (pinfunction "VREFDQ_H1") (pintype "power_in"))
      (node (ref "U10") (pin "M8") (pinfunction "VREFCA_M8") (pintype "power_in"))
      (node (ref "U9") (pin "H1") (pinfunction "VREFDQ_H1") (pintype "power_in"))
      (node (ref "U9") (pin "M8") (pinfunction "VREFCA_M8") (pintype "power_in"))
    )
    (net (code "82") (name "unconnected-(U9A-NC-PadJ1)") (class "Default")
      (node (ref "U9") (pin "J1") (pinfunction "NC_J1") (pintype "passive+no_connect"))
    )
    (net (code "83") (name "unconnected-(U9A-NC-PadJ9)") (class "Default")
      (node (ref "U9") (pin "J9") (pinfunction "NC_J9") (pintype "passive+no_connect"))
    )
    (net (code "84") (name "unconnected-(U9A-NC-PadL1)") (class "Default")
      (node (ref "U9") (pin "L1") (pinfunction "NC_L1") (pintype "passive+no_connect"))
    )
    (net (code "85") (name "unconnected-(U9A-NC-PadL9)") (class "Default")
      (node (ref "U9") (pin "L9") (pinfunction "NC_L9") (pintype "passive+no_connect"))
    )
    (net (code "86") (name "unconnected-(U9A-NC-PadM7)") (class "Default")
      (node (ref "U9") (pin "M7") (pinfunction "NC_M7") (pintype "passive+no_connect"))
    )
    (net (code "87") (name "unconnected-(U10A-NC-PadJ1)") (class "Default")
      (node (ref "U10") (pin "J1") (pinfunction "NC_J1") (pintype "passive+no_connect"))
    )
    (net (code "88") (name "unconnected-(U10A-NC-PadJ9)") (class "Default")
      (node (ref "U10") (pin "J9") (pinfunction "NC_J9") (pintype "passive+no_connect"))
    )
    (net (code "89") (name "unconnected-(U10A-NC-PadL1)") (class "Default")
      (node (ref "U10") (pin "L1") (pinfunction "NC_L1") (pintype "passive+no_connect"))
    )
    (net (code "90") (name "unconnected-(U10A-NC-PadL9)") (class "Default")
      (node (ref "U10") (pin "L9") (pinfunction "NC_L9") (pintype "passive+no_connect"))
    )
    (net (code "91") (name "unconnected-(U10A-NC-PadM7)") (class "Default")
      (node (ref "U10") (pin "M7") (pinfunction "NC_M7") (pintype "passive+no_connect"))
    )
  )
)
